# KX1_DB_EX_CONN.net
KiCad netlist of a schematic drawn in Altium Designer
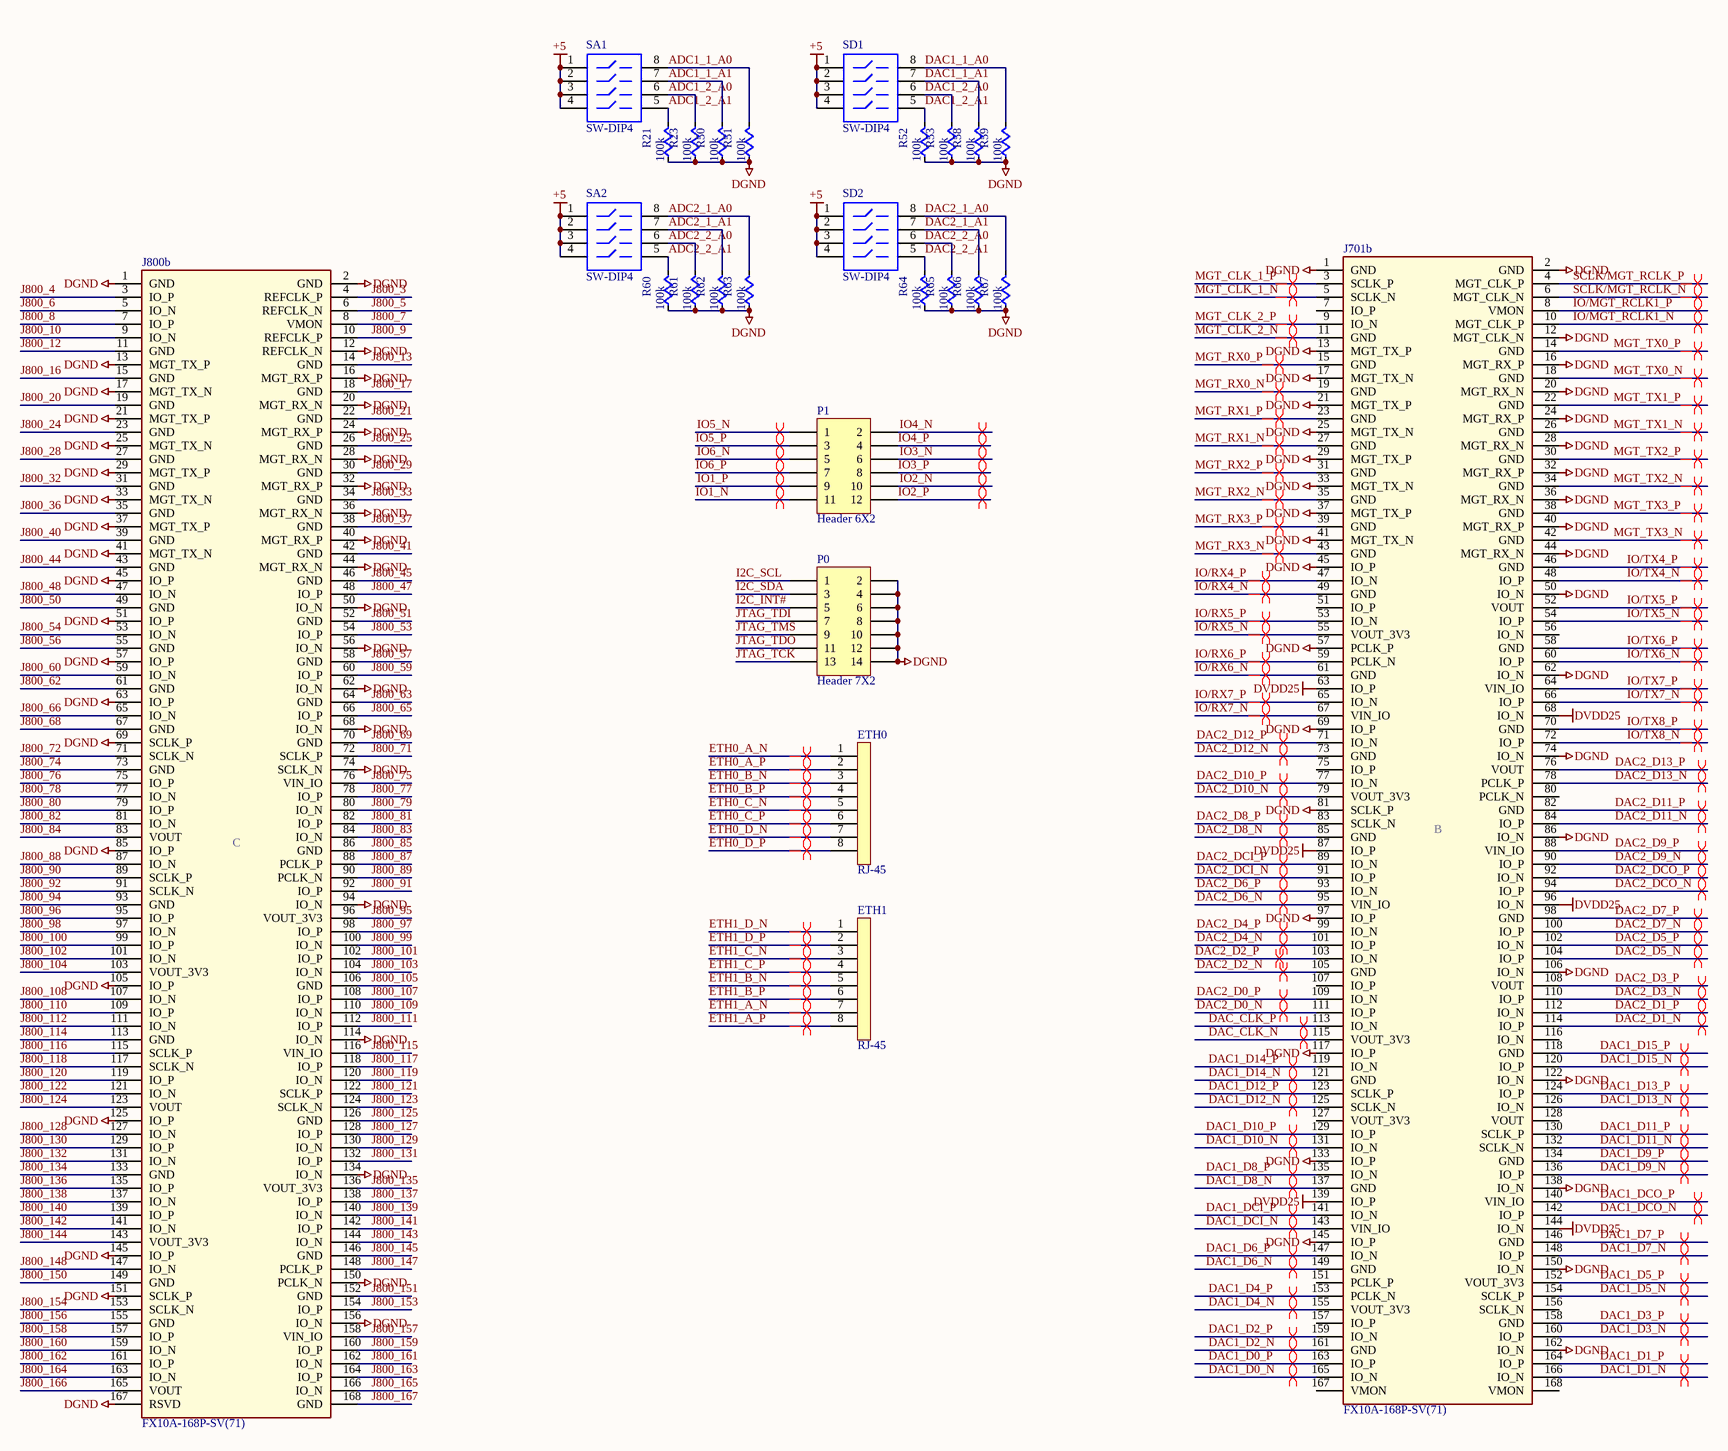
[diagram p0: KX1_DB_EX_CONN.SchDoc]

(export (version "E")
  (design (tool "Eeschema 10.0.6"))
  (components
    (comp (ref "ETH0")
      (value "RJ-45")
      (footprint "SMD_ETHERNET")
      (description "ethernet connector")
      (libsource (lib "KX1_DB") (part "SIP8"))
    )
    (comp (ref "ETH1")
      (value "RJ-45")
      (footprint "SMD_ETHERNET")
      (description "ethernet connector")
      (libsource (lib "KX1_DB") (part "SIP8"))
    )
    (comp (ref "J701b")
      (value "FX10A-168P-SV(71)")
      (footprint "Mercury_Baseboard_Connector")
      (description "Mercury Baseboard Connector")
      (fields
        (field (name "MANUFACTURER") "Hirose")
        (field (name "DISTPARTNUMBER") "FX10A-168P-SV(71)-ND")
        (field (name "CHECK SCH") "CG_2015-03-03")
      )
      (libsource (lib "Enclustra-Mars-Mercury-Altium-Library") (part "Mercury_Baseboard_Connector-B"))
    )
    (comp (ref "J800b")
      (value "FX10A-168P-SV(71)")
      (footprint "Mercury_Baseboard_Connector")
      (description "Mercury Baseboard Connector")
      (fields
        (field (name "MANUFACTURER") "Hirose")
        (field (name "DISTPARTNUMBER") "FX10A-168P-SV(71)-ND")
        (field (name "CHECK SCH") "CG_2015-03-03")
      )
      (libsource (lib "Enclustra-Mars-Mercury-Altium-Library") (part "Mercury_Baseboard_Connector-C"))
    )
    (comp (ref "P0")
      (value "Header 7X2")
      (footprint "HDR2X7")
      (description "Header, 7-Pin, Dual row")
      (fields (field (name "PUBLISHER") "Altium Limited"))
      (libsource (lib "Miscellaneous Connectors") (part "Header 7X2"))
    )
    (comp (ref "P1")
      (value "Header 6X2")
      (footprint "HDR2X6")
      (description "Header, 6-Pin, Dual row")
      (fields (field (name "PUBLISHER") "Altium Limited"))
      (libsource (lib "Miscellaneous Connectors") (part "Header 6X2"))
    )
    (comp (ref "R21")
      (value "100k")
      (footprint "0603w")
      (description "resistor")
      (fields
        (field (name "MANUFACTURER") "Yageo")
        (field (name "MANUFACTURER PART NUMBER") "RC0603FR-0776K8L")
      )
      (libsource (lib "KX1_DB") (part "RES_SM"))
    )
    (comp (ref "R23")
      (value "100k")
      (footprint "0603w")
      (description "resistor")
      (fields
        (field (name "MANUFACTURER") "Yageo")
        (field (name "MANUFACTURER PART NUMBER") "RC0603FR-0776K8L")
      )
      (libsource (lib "KX1_DB") (part "RES_SM"))
    )
    (comp (ref "R50")
      (value "100k")
      (footprint "0603w")
      (description "resistor")
      (fields
        (field (name "MANUFACTURER") "Yageo")
        (field (name "MANUFACTURER PART NUMBER") "RC0603FR-0776K8L")
      )
      (libsource (lib "KX1_DB") (part "RES_SM"))
    )
    (comp (ref "R51")
      (value "100k")
      (footprint "0603w")
      (description "resistor")
      (fields
        (field (name "MANUFACTURER") "Yageo")
        (field (name "MANUFACTURER PART NUMBER") "RC0603FR-0776K8L")
      )
      (libsource (lib "KX1_DB") (part "RES_SM"))
    )
    (comp (ref "R52")
      (value "100k")
      (footprint "0603w")
      (description "resistor")
      (fields
        (field (name "MANUFACTURER") "Yageo")
        (field (name "MANUFACTURER PART NUMBER") "RC0603FR-0776K8L")
      )
      (libsource (lib "KX1_DB") (part "RES_SM"))
    )
    (comp (ref "R53")
      (value "100k")
      (footprint "0603w")
      (description "resistor")
      (fields
        (field (name "MANUFACTURER") "Yageo")
        (field (name "MANUFACTURER PART NUMBER") "RC0603FR-0776K8L")
      )
      (libsource (lib "KX1_DB") (part "RES_SM"))
    )
    (comp (ref "R58")
      (value "100k")
      (footprint "0603w")
      (description "resistor")
      (fields
        (field (name "MANUFACTURER") "Yageo")
        (field (name "MANUFACTURER PART NUMBER") "RC0603FR-0776K8L")
      )
      (libsource (lib "KX1_DB") (part "RES_SM"))
    )
    (comp (ref "R59")
      (value "100k")
      (footprint "0603w")
      (description "resistor")
      (fields
        (field (name "MANUFACTURER") "Yageo")
        (field (name "MANUFACTURER PART NUMBER") "RC0603FR-0776K8L")
      )
      (libsource (lib "KX1_DB") (part "RES_SM"))
    )
    (comp (ref "R60")
      (value "100k")
      (footprint "0603w")
      (description "resistor")
      (fields
        (field (name "MANUFACTURER") "Yageo")
        (field (name "MANUFACTURER PART NUMBER") "RC0603FR-0776K8L")
      )
      (libsource (lib "KX1_DB") (part "RES_SM"))
    )
    (comp (ref "R61")
      (value "100k")
      (footprint "0603w")
      (description "resistor")
      (fields
        (field (name "MANUFACTURER") "Yageo")
        (field (name "MANUFACTURER PART NUMBER") "RC0603FR-0776K8L")
      )
      (libsource (lib "KX1_DB") (part "RES_SM"))
    )
    (comp (ref "R62")
      (value "100k")
      (footprint "0603w")
      (description "resistor")
      (fields
        (field (name "MANUFACTURER") "Yageo")
        (field (name "MANUFACTURER PART NUMBER") "RC0603FR-0776K8L")
      )
      (libsource (lib "KX1_DB") (part "RES_SM"))
    )
    (comp (ref "R63")
      (value "100k")
      (footprint "0603w")
      (description "resistor")
      (fields
        (field (name "MANUFACTURER") "Yageo")
        (field (name "MANUFACTURER PART NUMBER") "RC0603FR-0776K8L")
      )
      (libsource (lib "KX1_DB") (part "RES_SM"))
    )
    (comp (ref "R64")
      (value "100k")
      (footprint "0603w")
      (description "resistor")
      (fields
        (field (name "MANUFACTURER") "Yageo")
        (field (name "MANUFACTURER PART NUMBER") "RC0603FR-0776K8L")
      )
      (libsource (lib "KX1_DB") (part "RES_SM"))
    )
    (comp (ref "R65")
      (value "100k")
      (footprint "0603w")
      (description "resistor")
      (fields
        (field (name "MANUFACTURER") "Yageo")
        (field (name "MANUFACTURER PART NUMBER") "RC0603FR-0776K8L")
      )
      (libsource (lib "KX1_DB") (part "RES_SM"))
    )
    (comp (ref "R66")
      (value "100k")
      (footprint "0603w")
      (description "resistor")
      (fields
        (field (name "MANUFACTURER") "Yageo")
        (field (name "MANUFACTURER PART NUMBER") "RC0603FR-0776K8L")
      )
      (libsource (lib "KX1_DB") (part "RES_SM"))
    )
    (comp (ref "R67")
      (value "100k")
      (footprint "0603w")
      (description "resistor")
      (fields
        (field (name "MANUFACTURER") "Yageo")
        (field (name "MANUFACTURER PART NUMBER") "RC0603FR-0776K8L")
      )
      (libsource (lib "KX1_DB") (part "RES_SM"))
    )
    (comp (ref "SA1")
      (value "SW-DIP4")
      (footprint "DIP-8")
      (description "DIP Switch")
      (fields (field (name "PUBLISHER") "Altium Limited"))
      (libsource (lib "Miscellaneous Devices") (part "SW-DIP4"))
    )
    (comp (ref "SA2")
      (value "SW-DIP4")
      (footprint "DIP-8")
      (description "DIP Switch")
      (fields (field (name "PUBLISHER") "Altium Limited"))
      (libsource (lib "Miscellaneous Devices") (part "SW-DIP4"))
    )
    (comp (ref "SD1")
      (value "SW-DIP4")
      (footprint "DIP-8")
      (description "DIP Switch")
      (fields (field (name "PUBLISHER") "Altium Limited"))
      (libsource (lib "Miscellaneous Devices") (part "SW-DIP4"))
    )
    (comp (ref "SD2")
      (value "SW-DIP4")
      (footprint "DIP-8")
      (description "DIP Switch")
      (fields (field (name "PUBLISHER") "Altium Limited"))
      (libsource (lib "Miscellaneous Devices") (part "SW-DIP4"))
    )
  )
  (nets
    (net (code "1") (name "+5") (class "Default")
      (node (ref "SA1") (pin "1") (pinfunction "1_1") (pintype "passive"))
      (node (ref "SA1") (pin "2") (pinfunction "2_2") (pintype "passive"))
      (node (ref "SA1") (pin "3") (pinfunction "3_3") (pintype "passive"))
      (node (ref "SA1") (pin "4") (pinfunction "4_4") (pintype "passive"))
      (node (ref "SA2") (pin "1") (pinfunction "1_1") (pintype "passive"))
      (node (ref "SA2") (pin "2") (pinfunction "2_2") (pintype "passive"))
      (node (ref "SA2") (pin "3") (pinfunction "3_3") (pintype "passive"))
      (node (ref "SA2") (pin "4") (pinfunction "4_4") (pintype "passive"))
      (node (ref "SD1") (pin "1") (pinfunction "1_1") (pintype "passive"))
      (node (ref "SD1") (pin "2") (pinfunction "2_2") (pintype "passive"))
      (node (ref "SD1") (pin "3") (pinfunction "3_3") (pintype "passive"))
      (node (ref "SD1") (pin "4") (pinfunction "4_4") (pintype "passive"))
      (node (ref "SD2") (pin "1") (pinfunction "1_1") (pintype "passive"))
      (node (ref "SD2") (pin "2") (pinfunction "2_2") (pintype "passive"))
      (node (ref "SD2") (pin "3") (pinfunction "3_3") (pintype "passive"))
      (node (ref "SD2") (pin "4") (pinfunction "4_4") (pintype "passive"))
    )
    (net (code "2") (name "/ADC1_1_A0") (class "Default")
      (node (ref "R51") (pin "2") (pintype "passive"))
      (node (ref "SA1") (pin "8") (pinfunction "8_8") (pintype "passive"))
    )
    (net (code "3") (name "/ADC1_1_A1") (class "Default")
      (node (ref "R50") (pin "2") (pintype "passive"))
      (node (ref "SA1") (pin "7") (pinfunction "7_7") (pintype "passive"))
    )
    (net (code "4") (name "/ADC1_2_A0") (class "Default")
      (node (ref "R23") (pin "2") (pintype "passive"))
      (node (ref "SA1") (pin "6") (pinfunction "6_6") (pintype "passive"))
    )
    (net (code "5") (name "/ADC1_2_A1") (class "Default")
      (node (ref "R21") (pin "2") (pintype "passive"))
      (node (ref "SA1") (pin "5") (pinfunction "5_5") (pintype "passive"))
    )
    (net (code "6") (name "/ADC2_1_A0") (class "Default")
      (node (ref "R63") (pin "2") (pintype "passive"))
      (node (ref "SA2") (pin "8") (pinfunction "8_8") (pintype "passive"))
    )
    (net (code "7") (name "/ADC2_1_A1") (class "Default")
      (node (ref "R62") (pin "2") (pintype "passive"))
      (node (ref "SA2") (pin "7") (pinfunction "7_7") (pintype "passive"))
    )
    (net (code "8") (name "/ADC2_2_A0") (class "Default")
      (node (ref "R61") (pin "2") (pintype "passive"))
      (node (ref "SA2") (pin "6") (pinfunction "6_6") (pintype "passive"))
    )
    (net (code "9") (name "/ADC2_2_A1") (class "Default")
      (node (ref "R60") (pin "2") (pintype "passive"))
      (node (ref "SA2") (pin "5") (pinfunction "5_5") (pintype "passive"))
    )
    (net (code "10") (name "/DAC1_1_A0") (class "Default")
      (node (ref "R59") (pin "2") (pintype "passive"))
      (node (ref "SD1") (pin "8") (pinfunction "8_8") (pintype "passive"))
    )
    (net (code "11") (name "/DAC1_1_A1") (class "Default")
      (node (ref "R58") (pin "2") (pintype "passive"))
      (node (ref "SD1") (pin "7") (pinfunction "7_7") (pintype "passive"))
    )
    (net (code "12") (name "/DAC1_2_A0") (class "Default")
      (node (ref "R53") (pin "2") (pintype "passive"))
      (node (ref "SD1") (pin "6") (pinfunction "6_6") (pintype "passive"))
    )
    (net (code "13") (name "/DAC1_2_A1") (class "Default")
      (node (ref "R52") (pin "2") (pintype "passive"))
      (node (ref "SD1") (pin "5") (pinfunction "5_5") (pintype "passive"))
    )
    (net (code "14") (name "/DAC1_D0_N") (class "Default")
      (node (ref "J701b") (pin "165") (pinfunction "IO_N_165") (pintype "passive"))
    )
    (net (code "15") (name "/DAC1_D0_P") (class "Default")
      (node (ref "J701b") (pin "163") (pinfunction "IO_P_163") (pintype "passive"))
    )
    (net (code "16") (name "/DAC1_D1_N") (class "Default")
      (node (ref "J701b") (pin "166") (pinfunction "IO_N_166") (pintype "passive"))
    )
    (net (code "17") (name "/DAC1_D1_P") (class "Default")
      (node (ref "J701b") (pin "164") (pinfunction "IO_P_164") (pintype "passive"))
    )
    (net (code "18") (name "/DAC1_D2_N") (class "Default")
      (node (ref "J701b") (pin "161") (pinfunction "GND_161") (pintype "passive"))
    )
    (net (code "19") (name "/DAC1_D2_P") (class "Default")
      (node (ref "J701b") (pin "159") (pinfunction "IO_N_159") (pintype "passive"))
    )
    (net (code "20") (name "/DAC1_D3_N") (class "Default")
      (node (ref "J701b") (pin "160") (pinfunction "IO_P_160") (pintype "passive"))
    )
    (net (code "21") (name "/DAC1_D3_P") (class "Default")
      (node (ref "J701b") (pin "158") (pinfunction "GND_158") (pintype "passive"))
    )
    (net (code "22") (name "/DAC1_D4_N") (class "Default")
      (node (ref "J701b") (pin "155") (pinfunction "VOUT_3V3_155") (pintype "passive"))
    )
    (net (code "23") (name "/DAC1_D4_P") (class "Default")
      (node (ref "J701b") (pin "153") (pinfunction "PCLK_N_153") (pintype "passive"))
    )
    (net (code "24") (name "/DAC1_D5_N") (class "Default")
      (node (ref "J701b") (pin "154") (pinfunction "SCLK_P_154") (pintype "passive"))
    )
    (net (code "25") (name "/DAC1_D5_P") (class "Default")
      (node (ref "J701b") (pin "152") (pinfunction "VOUT_3V3_152") (pintype "passive"))
    )
    (net (code "26") (name "/DAC1_D6_N") (class "Default")
      (node (ref "J701b") (pin "149") (pinfunction "GND_149") (pintype "passive"))
    )
    (net (code "27") (name "/DAC1_D6_P") (class "Default")
      (node (ref "J701b") (pin "147") (pinfunction "IO_N_147") (pintype "passive"))
    )
    (net (code "28") (name "/DAC1_D7_N") (class "Default")
      (node (ref "J701b") (pin "148") (pinfunction "IO_P_148") (pintype "passive"))
    )
    (net (code "29") (name "/DAC1_D7_P") (class "Default")
      (node (ref "J701b") (pin "146") (pinfunction "GND_146") (pintype "passive"))
    )
    (net (code "30") (name "/DAC1_D8_N") (class "Default")
      (node (ref "J701b") (pin "137") (pinfunction "GND_137") (pintype "passive"))
    )
    (net (code "31") (name "/DAC1_D8_P") (class "Default")
      (node (ref "J701b") (pin "135") (pinfunction "IO_N_135") (pintype "passive"))
    )
    (net (code "32") (name "/DAC1_D9_N") (class "Default")
      (node (ref "J701b") (pin "136") (pinfunction "IO_P_136") (pintype "passive"))
    )
    (net (code "33") (name "/DAC1_D9_P") (class "Default")
      (node (ref "J701b") (pin "134") (pinfunction "GND_134") (pintype "passive"))
    )
    (net (code "34") (name "/DAC1_D10_N") (class "Default")
      (node (ref "J701b") (pin "131") (pinfunction "IO_N_131") (pintype "passive"))
    )
    (net (code "35") (name "/DAC1_D10_P") (class "Default")
      (node (ref "J701b") (pin "129") (pinfunction "IO_P_129") (pintype "passive"))
    )
    (net (code "36") (name "/DAC1_D11_N") (class "Default")
      (node (ref "J701b") (pin "132") (pinfunction "SCLK_N_132") (pintype "passive"))
    )
    (net (code "37") (name "/DAC1_D11_P") (class "Default")
      (node (ref "J701b") (pin "130") (pinfunction "SCLK_P_130") (pintype "passive"))
    )
    (net (code "38") (name "/DAC1_D12_N") (class "Default")
      (node (ref "J701b") (pin "125") (pinfunction "SCLK_N_125") (pintype "passive"))
    )
    (net (code "39") (name "/DAC1_D12_P") (class "Default")
      (node (ref "J701b") (pin "123") (pinfunction "SCLK_P_123") (pintype "passive"))
    )
    (net (code "40") (name "/DAC1_D13_N") (class "Default")
      (node (ref "J701b") (pin "126") (pinfunction "IO_N_126") (pintype "passive"))
    )
    (net (code "41") (name "/DAC1_D13_P") (class "Default")
      (node (ref "J701b") (pin "124") (pinfunction "IO_P_124") (pintype "passive"))
    )
    (net (code "42") (name "/DAC1_D14_N") (class "Default")
      (node (ref "J701b") (pin "121") (pinfunction "GND_121") (pintype "passive"))
    )
    (net (code "43") (name "/DAC1_D14_P") (class "Default")
      (node (ref "J701b") (pin "119") (pinfunction "IO_N_119") (pintype "passive"))
    )
    (net (code "44") (name "/DAC1_D15_N") (class "Default")
      (node (ref "J701b") (pin "120") (pinfunction "IO_P_120") (pintype "passive"))
    )
    (net (code "45") (name "/DAC1_D15_P") (class "Default")
      (node (ref "J701b") (pin "118") (pinfunction "GND_118") (pintype "passive"))
    )
    (net (code "46") (name "/DAC1_DCI_N") (class "Default")
      (node (ref "J701b") (pin "143") (pinfunction "VIN_IO_143") (pintype "passive"))
    )
    (net (code "47") (name "/DAC1_DCI_P") (class "Default")
      (node (ref "J701b") (pin "141") (pinfunction "IO_N_141") (pintype "passive"))
    )
    (net (code "48") (name "/DAC1_DCO_N") (class "Default")
      (node (ref "J701b") (pin "142") (pinfunction "IO_P_142") (pintype "passive"))
    )
    (net (code "49") (name "/DAC1_DCO_P") (class "Default")
      (node (ref "J701b") (pin "140") (pinfunction "VIN_IO_140") (pintype "passive"))
    )
    (net (code "50") (name "/DAC2_1_A0") (class "Default")
      (node (ref "R67") (pin "2") (pintype "passive"))
      (node (ref "SD2") (pin "8") (pinfunction "8_8") (pintype "passive"))
    )
    (net (code "51") (name "/DAC2_1_A1") (class "Default")
      (node (ref "R66") (pin "2") (pintype "passive"))
      (node (ref "SD2") (pin "7") (pinfunction "7_7") (pintype "passive"))
    )
    (net (code "52") (name "/DAC2_2_A0") (class "Default")
      (node (ref "R65") (pin "2") (pintype "passive"))
      (node (ref "SD2") (pin "6") (pinfunction "6_6") (pintype "passive"))
    )
    (net (code "53") (name "/DAC2_2_A1") (class "Default")
      (node (ref "R64") (pin "2") (pintype "passive"))
      (node (ref "SD2") (pin "5") (pinfunction "5_5") (pintype "passive"))
    )
    (net (code "54") (name "/DAC2_D0_N") (class "Default")
      (node (ref "J701b") (pin "111") (pinfunction "IO_P_111") (pintype "passive"))
    )
    (net (code "55") (name "/DAC2_D0_P") (class "Default")
      (node (ref "J701b") (pin "109") (pinfunction "IO_N_109") (pintype "passive"))
    )
    (net (code "56") (name "/DAC2_D1_N") (class "Default")
      (node (ref "J701b") (pin "114") (pinfunction "IO_P_114") (pintype "passive"))
    )
    (net (code "57") (name "/DAC2_D1_P") (class "Default")
      (node (ref "J701b") (pin "112") (pinfunction "IO_N_112") (pintype "passive"))
    )
    (net (code "58") (name "/DAC2_D2_N") (class "Default")
      (node (ref "J701b") (pin "105") (pinfunction "GND_105") (pintype "passive"))
    )
    (net (code "59") (name "/DAC2_D2_P") (class "Default")
      (node (ref "J701b") (pin "103") (pinfunction "IO_N_103") (pintype "passive"))
    )
    (net (code "60") (name "/DAC2_D3_N") (class "Default")
      (node (ref "J701b") (pin "110") (pinfunction "IO_P_110") (pintype "passive"))
    )
    (net (code "61") (name "/DAC2_D3_P") (class "Default")
      (node (ref "J701b") (pin "108") (pinfunction "VOUT_108") (pintype "passive"))
    )
    (net (code "62") (name "/DAC2_D4_N") (class "Default")
      (node (ref "J701b") (pin "101") (pinfunction "IO_P_101") (pintype "passive"))
    )
    (net (code "63") (name "/DAC2_D4_P") (class "Default")
      (node (ref "J701b") (pin "99") (pinfunction "IO_N_99") (pintype "passive"))
    )
    (net (code "64") (name "/DAC2_D5_N") (class "Default")
      (node (ref "J701b") (pin "104") (pinfunction "IO_P_104") (pintype "passive"))
    )
    (net (code "65") (name "/DAC2_D5_P") (class "Default")
      (node (ref "J701b") (pin "102") (pinfunction "IO_N_102") (pintype "passive"))
    )
    (net (code "66") (name "/DAC2_D6_N") (class "Default")
      (node (ref "J701b") (pin "95") (pinfunction "VIN_IO_95") (pintype "passive"))
    )
    (net (code "67") (name "/DAC2_D6_P") (class "Default")
      (node (ref "J701b") (pin "93") (pinfunction "IO_N_93") (pintype "passive"))
    )
    (net (code "68") (name "/DAC2_D7_N") (class "Default")
      (node (ref "J701b") (pin "100") (pinfunction "IO_P_100") (pintype "passive"))
    )
    (net (code "69") (name "/DAC2_D7_P") (class "Default")
      (node (ref "J701b") (pin "98") (pinfunction "GND_98") (pintype "passive"))
    )
    (net (code "70") (name "/DAC2_D8_N") (class "Default")
      (node (ref "J701b") (pin "85") (pinfunction "GND_85") (pintype "passive"))
    )
    (net (code "71") (name "/DAC2_D8_P") (class "Default")
      (node (ref "J701b") (pin "83") (pinfunction "SCLK_N_83") (pintype "passive"))
    )
    (net (code "72") (name "/DAC2_D9_N") (class "Default")
      (node (ref "J701b") (pin "90") (pinfunction "IO_P_90") (pintype "passive"))
    )
    (net (code "73") (name "/DAC2_D9_P") (class "Default")
      (node (ref "J701b") (pin "88") (pinfunction "VIN_IO_88") (pintype "passive"))
    )
    (net (code "74") (name "/DAC2_D10_N") (class "Default")
      (node (ref "J701b") (pin "79") (pinfunction "VOUT_3V3_79") (pintype "passive"))
    )
    (net (code "75") (name "/DAC2_D10_P") (class "Default")
      (node (ref "J701b") (pin "77") (pinfunction "IO_N_77") (pintype "passive"))
    )
    (net (code "76") (name "/DAC2_D11_N") (class "Default")
      (node (ref "J701b") (pin "84") (pinfunction "IO_P_84") (pintype "passive"))
    )
    (net (code "77") (name "/DAC2_D11_P") (class "Default")
      (node (ref "J701b") (pin "82") (pinfunction "GND_82") (pintype "passive"))
    )
    (net (code "78") (name "/DAC2_D12_N") (class "Default")
      (node (ref "J701b") (pin "73") (pinfunction "GND_73") (pintype "passive"))
    )
    (net (code "79") (name "/DAC2_D12_P") (class "Default")
      (node (ref "J701b") (pin "71") (pinfunction "IO_N_71") (pintype "passive"))
    )
    (net (code "80") (name "/DAC2_D13_N") (class "Default")
      (node (ref "J701b") (pin "78") (pinfunction "PCLK_P_78") (pintype "passive"))
    )
    (net (code "81") (name "/DAC2_D13_P") (class "Default")
      (node (ref "J701b") (pin "76") (pinfunction "VOUT_76") (pintype "passive"))
    )
    (net (code "82") (name "/DAC2_DCI_N") (class "Default")
      (node (ref "J701b") (pin "91") (pinfunction "IO_P_91") (pintype "passive"))
    )
    (net (code "83") (name "/DAC2_DCI_P") (class "Default")
      (node (ref "J701b") (pin "89") (pinfunction "IO_N_89") (pintype "passive"))
    )
    (net (code "84") (name "/DAC2_DCO_N") (class "Default")
      (node (ref "J701b") (pin "94") (pinfunction "IO_P_94") (pintype "passive"))
    )
    (net (code "85") (name "/DAC2_DCO_P") (class "Default")
      (node (ref "J701b") (pin "92") (pinfunction "IO_N_92") (pintype "passive"))
    )
    (net (code "86") (name "/DAC_CLK_N") (class "Default")
      (node (ref "J701b") (pin "115") (pinfunction "VOUT_3V3_115") (pintype "passive"))
    )
    (net (code "87") (name "/DAC_CLK_P") (class "Default")
      (node (ref "J701b") (pin "113") (pinfunction "IO_N_113") (pintype "passive"))
    )
    (net (code "88") (name "/ETH0_A_N") (class "Default") (node (ref "ETH0") (pin "1") (pintype "passive")))
    (net (code "89") (name "/ETH0_A_P") (class "Default") (node (ref "ETH0") (pin "2") (pintype "passive")))
    (net (code "90") (name "/ETH0_B_N") (class "Default") (node (ref "ETH0") (pin "3") (pintype "passive")))
    (net (code "91") (name "/ETH0_B_P") (class "Default") (node (ref "ETH0") (pin "4") (pintype "passive")))
    (net (code "92") (name "/ETH0_C_N") (class "Default") (node (ref "ETH0") (pin "5") (pintype "passive")))
    (net (code "93") (name "/ETH0_C_P") (class "Default") (node (ref "ETH0") (pin "6") (pintype "passive")))
    (net (code "94") (name "/ETH0_D_N") (class "Default") (node (ref "ETH0") (pin "7") (pintype "passive")))
    (net (code "95") (name "/ETH0_D_P") (class "Default") (node (ref "ETH0") (pin "8") (pintype "passive")))
    (net (code "96") (name "/ETH1_A_N") (class "Default") (node (ref "ETH1") (pin "7") (pintype "passive")))
    (net (code "97") (name "/ETH1_A_P") (class "Default") (node (ref "ETH1") (pin "8") (pintype "passive")))
    (net (code "98") (name "/ETH1_B_N") (class "Default") (node (ref "ETH1") (pin "5") (pintype "passive")))
    (net (code "99") (name "/ETH1_B_P") (class "Default") (node (ref "ETH1") (pin "6") (pintype "passive")))
    (net (code "100") (name "/ETH1_C_N") (class "Default") (node (ref "ETH1") (pin "3") (pintype "passive")))
    (net (code "101") (name "/ETH1_C_P") (class "Default") (node (ref "ETH1") (pin "4") (pintype "passive")))
    (net (code "102") (name "/ETH1_D_N") (class "Default") (node (ref "ETH1") (pin "1") (pintype "passive")))
    (net (code "103") (name "/ETH1_D_P") (class "Default") (node (ref "ETH1") (pin "2") (pintype "passive")))
    (net (code "104") (name "/I2C_INT#") (class "Default")
      (node (ref "P0") (pin "5") (pinfunction "5_5") (pintype "passive"))
    )
    (net (code "105") (name "/I2C_SCL") (class "Default")
      (node (ref "P0") (pin "1") (pinfunction "1_1") (pintype "passive"))
    )
    (net (code "106") (name "/I2C_SDA") (class "Default")
      (node (ref "P0") (pin "3") (pinfunction "3_3") (pintype "passive"))
    )
    (net (code "107") (name "/IO1_N") (class "Default")
      (node (ref "P1") (pin "11") (pinfunction "11_11") (pintype "passive"))
    )
    (net (code "108") (name "/IO1_P") (class "Default")
      (node (ref "P1") (pin "9") (pinfunction "9_9") (pintype "passive"))
    )
    (net (code "109") (name "/IO2_N") (class "Default")
      (node (ref "P1") (pin "10") (pinfunction "10_10") (pintype "passive"))
    )
    (net (code "110") (name "/IO2_P") (class "Default")
      (node (ref "P1") (pin "12") (pinfunction "12_12") (pintype "passive"))
    )
    (net (code "111") (name "/IO3_N") (class "Default")
      (node (ref "P1") (pin "6") (pinfunction "6_6") (pintype "passive"))
    )
    (net (code "112") (name "/IO3_P") (class "Default")
      (node (ref "P1") (pin "8") (pinfunction "8_8") (pintype "passive"))
    )
    (net (code "113") (name "/IO4_N") (class "Default")
      (node (ref "P1") (pin "2") (pinfunction "2_2") (pintype "passive"))
    )
    (net (code "114") (name "/IO4_P") (class "Default")
      (node (ref "P1") (pin "4") (pinfunction "4_4") (pintype "passive"))
    )
    (net (code "115") (name "/IO5_N") (class "Default")
      (node (ref "P1") (pin "1") (pinfunction "1_1") (pintype "passive"))
    )
    (net (code "116") (name "/IO5_P") (class "Default")
      (node (ref "P1") (pin "3") (pinfunction "3_3") (pintype "passive"))
    )
    (net (code "117") (name "/IO6_N") (class "Default")
      (node (ref "P1") (pin "5") (pinfunction "5_5") (pintype "passive"))
    )
    (net (code "118") (name "/IO6_P") (class "Default")
      (node (ref "P1") (pin "7") (pinfunction "7_7") (pintype "passive"))
    )
    (net (code "119") (name "/IO{slash}MGT_RCLK1_N") (class "Default")
      (node (ref "J701b") (pin "10") (pinfunction "MGT_CLK_P_10") (pintype "passive"))
    )
    (net (code "120") (name "/IO{slash}MGT_RCLK1_P") (class "Default")
      (node (ref "J701b") (pin "8") (pinfunction "VMON_8") (pintype "passive"))
    )
    (net (code "121") (name "/IO{slash}RX4_N") (class "Default")
      (node (ref "J701b") (pin "49") (pinfunction "GND_49") (pintype "passive"))
    )
    (net (code "122") (name "/IO{slash}RX4_P") (class "Default")
      (node (ref "J701b") (pin "47") (pinfunction "IO_N_47") (pintype "passive"))
    )
    (net (code "123") (name "/IO{slash}RX5_N") (class "Default")
      (node (ref "J701b") (pin "55") (pinfunction "VOUT_3V3_55") (pintype "passive"))
    )
    (net (code "124") (name "/IO{slash}RX5_P") (class "Default")
      (node (ref "J701b") (pin "53") (pinfunction "IO_N_53") (pintype "passive"))
    )
    (net (code "125") (name "/IO{slash}RX6_N") (class "Default")
      (node (ref "J701b") (pin "61") (pinfunction "GND_61") (pintype "passive"))
    )
    (net (code "126") (name "/IO{slash}RX6_P") (class "Default")
      (node (ref "J701b") (pin "59") (pinfunction "PCLK_N_59") (pintype "passive"))
    )
    (net (code "127") (name "/IO{slash}RX7_N") (class "Default")
      (node (ref "J701b") (pin "67") (pinfunction "VIN_IO_67") (pintype "passive"))
    )
    (net (code "128") (name "/IO{slash}RX7_P") (class "Default")
      (node (ref "J701b") (pin "65") (pinfunction "IO_N_65") (pintype "passive"))
    )
    (net (code "129") (name "/IO{slash}TX4_N") (class "Default")
      (node (ref "J701b") (pin "48") (pinfunction "IO_P_48") (pintype "passive"))
    )
    (net (code "130") (name "/IO{slash}TX4_P") (class "Default")
      (node (ref "J701b") (pin "46") (pinfunction "GND_46") (pintype "passive"))
    )
    (net (code "131") (name "/IO{slash}TX5_N") (class "Default")
      (node (ref "J701b") (pin "54") (pinfunction "IO_P_54") (pintype "passive"))
    )
    (net (code "132") (name "/IO{slash}TX5_P") (class "Default")
      (node (ref "J701b") (pin "52") (pinfunction "VOUT_52") (pintype "passive"))
    )
    (net (code "133") (name "/IO{slash}TX6_N") (class "Default")
      (node (ref "J701b") (pin "60") (pinfunction "IO_P_60") (pintype "passive"))
    )
    (net (code "134") (name "/IO{slash}TX6_P") (class "Default")
      (node (ref "J701b") (pin "58") (pinfunction "GND_58") (pintype "passive"))
    )
    (net (code "135") (name "/IO{slash}TX7_N") (class "Default")
      (node (ref "J701b") (pin "66") (pinfunction "IO_P_66") (pintype "passive"))
    )
    (net (code "136") (name "/IO{slash}TX7_P") (class "Default")
      (node (ref "J701b") (pin "64") (pinfunction "VIN_IO_64") (pintype "passive"))
    )
    (net (code "137") (name "/IO{slash}TX8_N") (class "Default")
      (node (ref "J701b") (pin "72") (pinfunction "IO_P_72") (pintype "passive"))
    )
    (net (code "138") (name "/IO{slash}TX8_P") (class "Default")
      (node (ref "J701b") (pin "70") (pinfunction "GND_70") (pintype "passive"))
    )
    (net (code "139") (name "/J800_3") (class "Default")
      (node (ref "J800b") (pin "4") (pinfunction "REFCLK_P_4") (pintype "passive"))
    )
    (net (code "140") (name "/J800_4") (class "Default")
      (node (ref "J800b") (pin "3") (pinfunction "IO_P_3") (pintype "passive"))
    )
    (net (code "141") (name "/J800_5") (class "Default")
      (node (ref "J800b") (pin "6") (pinfunction "REFCLK_N_6") (pintype "passive"))
    )
    (net (code "142") (name "/J800_6") (class "Default")
      (node (ref "J800b") (pin "5") (pinfunction "IO_N_5") (pintype "passive"))
    )
    (net (code "143") (name "/J800_7") (class "Default")
      (node (ref "J800b") (pin "8") (pinfunction "VMON_8") (pintype "passive"))
    )
    (net (code "144") (name "/J800_8") (class "Default")
      (node (ref "J800b") (pin "7") (pinfunction "IO_P_7") (pintype "passive"))
    )
    (net (code "145") (name "/J800_9") (class "Default")
      (node (ref "J800b") (pin "10") (pinfunction "REFCLK_P_10") (pintype "passive"))
    )
    (net (code "146") (name "/J800_10") (class "Default")
      (node (ref "J800b") (pin "9") (pinfunction "IO_N_9") (pintype "passive"))
    )
    (net (code "147") (name "/J800_12") (class "Default")
      (node (ref "J800b") (pin "11") (pinfunction "GND_11") (pintype "passive"))
    )
    (net (code "148") (name "/J800_13") (class "Default")
      (node (ref "J800b") (pin "14") (pinfunction "GND_14") (pintype "passive"))
    )
    (net (code "149") (name "/J800_16") (class "Default")
      (node (ref "J800b") (pin "15") (pinfunction "GND_15") (pintype "passive"))
    )
    (net (code "150") (name "/J800_17") (class "Default")
      (node (ref "J800b") (pin "18") (pinfunction "GND_18") (pintype "passive"))
    )
    (net (code "151") (name "/J800_20") (class "Default")
      (node (ref "J800b") (pin "19") (pinfunction "GND_19") (pintype "passive"))
    )
    (net (code "152") (name "/J800_21") (class "Default")
      (node (ref "J800b") (pin "22") (pinfunction "GND_22") (pintype "passive"))
    )
    (net (code "153") (name "/J800_24") (class "Default")
      (node (ref "J800b") (pin "23") (pinfunction "GND_23") (pintype "passive"))
    )
    (net (code "154") (name "/J800_25") (class "Default")
      (node (ref "J800b") (pin "26") (pinfunction "GND_26") (pintype "passive"))
    )
    (net (code "155") (name "/J800_28") (class "Default")
      (node (ref "J800b") (pin "27") (pinfunction "GND_27") (pintype "passive"))
    )
    (net (code "156") (name "/J800_29") (class "Default")
      (node (ref "J800b") (pin "30") (pinfunction "GND_30") (pintype "passive"))
    )
    (net (code "157") (name "/J800_32") (class "Default")
      (node (ref "J800b") (pin "31") (pinfunction "GND_31") (pintype "passive"))
    )
    (net (code "158") (name "/J800_33") (class "Default")
      (node (ref "J800b") (pin "34") (pinfunction "GND_34") (pintype "passive"))
    )
    (net (code "159") (name "/J800_36") (class "Default")
      (node (ref "J800b") (pin "35") (pinfunction "GND_35") (pintype "passive"))
    )
    (net (code "160") (name "/J800_37") (class "Default")
      (node (ref "J800b") (pin "38") (pinfunction "GND_38") (pintype "passive"))
    )
    (net (code "161") (name "/J800_40") (class "Default")
      (node (ref "J800b") (pin "39") (pinfunction "GND_39") (pintype "passive"))
    )
    (net (code "162") (name "/J800_41") (class "Default")
      (node (ref "J800b") (pin "42") (pinfunction "GND_42") (pintype "passive"))
    )
    (net (code "163") (name "/J800_44") (class "Default")
      (node (ref "J800b") (pin "43") (pinfunction "GND_43") (pintype "passive"))
    )
    (net (code "164") (name "/J800_45") (class "Default")
      (node (ref "J800b") (pin "46") (pinfunction "GND_46") (pintype "passive"))
    )
    (net (code "165") (name "/J800_47") (class "Default")
      (node (ref "J800b") (pin "48") (pinfunction "IO_P_48") (pintype "passive"))
    )
    (net (code "166") (name "/J800_48") (class "Default")
      (node (ref "J800b") (pin "47") (pinfunction "IO_N_47") (pintype "passive"))
    )
    (net (code "167") (name "/J800_50") (class "Default")
      (node (ref "J800b") (pin "49") (pinfunction "GND_49") (pintype "passive"))
    )
    (net (code "168") (name "/J800_51") (class "Default")
      (node (ref "J800b") (pin "52") (pinfunction "GND_52") (pintype "passive"))
    )
    (net (code "169") (name "/J800_53") (class "Default")
      (node (ref "J800b") (pin "54") (pinfunction "IO_P_54") (pintype "passive"))
    )
    (net (code "170") (name "/J800_54") (class "Default")
      (node (ref "J800b") (pin "53") (pinfunction "IO_N_53") (pintype "passive"))
    )
    (net (code "171") (name "/J800_56") (class "Default")
      (node (ref "J800b") (pin "55") (pinfunction "GND_55") (pintype "passive"))
    )
    (net (code "172") (name "/J800_57") (class "Default")
      (node (ref "J800b") (pin "58") (pinfunction "GND_58") (pintype "passive"))
    )
    (net (code "173") (name "/J800_59") (class "Default")
      (node (ref "J800b") (pin "60") (pinfunction "IO_P_60") (pintype "passive"))
    )
    (net (code "174") (name "/J800_60") (class "Default")
      (node (ref "J800b") (pin "59") (pinfunction "IO_N_59") (pintype "passive"))
    )
    (net (code "175") (name "/J800_62") (class "Default")
      (node (ref "J800b") (pin "61") (pinfunction "GND_61") (pintype "passive"))
    )
    (net (code "176") (name "/J800_63") (class "Default")
      (node (ref "J800b") (pin "64") (pinfunction "GND_64") (pintype "passive"))
    )
    (net (code "177") (name "/J800_65") (class "Default")
      (node (ref "J800b") (pin "66") (pinfunction "IO_P_66") (pintype "passive"))
    )
    (net (code "178") (name "/J800_66") (class "Default")
      (node (ref "J800b") (pin "65") (pinfunction "IO_N_65") (pintype "passive"))
    )
    (net (code "179") (name "/J800_68") (class "Default")
      (node (ref "J800b") (pin "67") (pinfunction "GND_67") (pintype "passive"))
    )
    (net (code "180") (name "/J800_69") (class "Default")
      (node (ref "J800b") (pin "70") (pinfunction "GND_70") (pintype "passive"))
    )
    (net (code "181") (name "/J800_71") (class "Default")
      (node (ref "J800b") (pin "72") (pinfunction "SCLK_P_72") (pintype "passive"))
    )
    (net (code "182") (name "/J800_72") (class "Default")
      (node (ref "J800b") (pin "71") (pinfunction "SCLK_N_71") (pintype "passive"))
    )
    (net (code "183") (name "/J800_74") (class "Default")
      (node (ref "J800b") (pin "73") (pinfunction "GND_73") (pintype "passive"))
    )
    (net (code "184") (name "/J800_75") (class "Default")
      (node (ref "J800b") (pin "76") (pinfunction "VIN_IO_76") (pintype "passive"))
    )
    (net (code "185") (name "/J800_76") (class "Default")
      (node (ref "J800b") (pin "75") (pinfunction "IO_P_75") (pintype "passive"))
    )
    (net (code "186") (name "/J800_77") (class "Default")
      (node (ref "J800b") (pin "78") (pinfunction "IO_P_78") (pintype "passive"))
    )
    (net (code "187") (name "/J800_78") (class "Default")
      (node (ref "J800b") (pin "77") (pinfunction "IO_N_77") (pintype "passive"))
    )
    (net (code "188") (name "/J800_79") (class "Default")
      (node (ref "J800b") (pin "80") (pinfunction "IO_N_80") (pintype "passive"))
    )
    (net (code "189") (name "/J800_80") (class "Default")
      (node (ref "J800b") (pin "79") (pinfunction "IO_P_79") (pintype "passive"))
    )
    (net (code "190") (name "/J800_81") (class "Default")
      (node (ref "J800b") (pin "82") (pinfunction "IO_P_82") (pintype "passive"))
    )
    (net (code "191") (name "/J800_82") (class "Default")
      (node (ref "J800b") (pin "81") (pinfunction "IO_N_81") (pintype "passive"))
    )
    (net (code "192") (name "/J800_83") (class "Default")
      (node (ref "J800b") (pin "84") (pinfunction "IO_N_84") (pintype "passive"))
    )
    (net (code "193") (name "/J800_84") (class "Default")
      (node (ref "J800b") (pin "83") (pinfunction "VOUT_83") (pintype "passive"))
    )
    (net (code "194") (name "/J800_85") (class "Default")
      (node (ref "J800b") (pin "86") (pinfunction "GND_86") (pintype "passive"))
    )
    (net (code "195") (name "/J800_87") (class "Default")
      (node (ref "J800b") (pin "88") (pinfunction "PCLK_P_88") (pintype "passive"))
    )
    (net (code "196") (name "/J800_88") (class "Default")
      (node (ref "J800b") (pin "87") (pinfunction "IO_N_87") (pintype "passive"))
    )
    (net (code "197") (name "/J800_89") (class "Default")
      (node (ref "J800b") (pin "90") (pinfunction "PCLK_N_90") (pintype "passive"))
    )
    (net (code "198") (name "/J800_90") (class "Default")
      (node (ref "J800b") (pin "89") (pinfunction "SCLK_P_89") (pintype "passive"))
    )
    (net (code "199") (name "/J800_91") (class "Default")
      (node (ref "J800b") (pin "92") (pinfunction "IO_P_92") (pintype "passive"))
    )
    (net (code "200") (name "/J800_92") (class "Default")
      (node (ref "J800b") (pin "91") (pinfunction "SCLK_N_91") (pintype "passive"))
    )
    (net (code "201") (name "/J800_94") (class "Default")
      (node (ref "J800b") (pin "93") (pinfunction "GND_93") (pintype "passive"))
    )
    (net (code "202") (name "/J800_95") (class "Default")
      (node (ref "J800b") (pin "96") (pinfunction "VOUT_3V3_96") (pintype "passive"))
    )
    (net (code "203") (name "/J800_96") (class "Default")
      (node (ref "J800b") (pin "95") (pinfunction "IO_P_95") (pintype "passive"))
    )
    (net (code "204") (name "/J800_97") (class "Default")
      (node (ref "J800b") (pin "98") (pinfunction "IO_P_98") (pintype "passive"))
    )
    (net (code "205") (name "/J800_98") (class "Default")
      (node (ref "J800b") (pin "97") (pinfunction "IO_N_97") (pintype "passive"))
    )
    (net (code "206") (name "/J800_99") (class "Default")
      (node (ref "J800b") (pin "100") (pinfunction "IO_N_100") (pintype "passive"))
    )
    (net (code "207") (name "/J800_100") (class "Default")
      (node (ref "J800b") (pin "99") (pinfunction "IO_P_99") (pintype "passive"))
    )
    (net (code "208") (name "/J800_101") (class "Default")
      (node (ref "J800b") (pin "102") (pinfunction "IO_P_102") (pintype "passive"))
    )
    (net (code "209") (name "/J800_102") (class "Default")
      (node (ref "J800b") (pin "101") (pinfunction "IO_N_101") (pintype "passive"))
    )
    (net (code "210") (name "/J800_103") (class "Default")
      (node (ref "J800b") (pin "104") (pinfunction "IO_N_104") (pintype "passive"))
    )
    (net (code "211") (name "/J800_104") (class "Default")
      (node (ref "J800b") (pin "103") (pinfunction "VOUT_3V3_103") (pintype "passive"))
    )
    (net (code "212") (name "/J800_105") (class "Default")
      (node (ref "J800b") (pin "106") (pinfunction "GND_106") (pintype "passive"))
    )
    (net (code "213") (name "/J800_107") (class "Default")
      (node (ref "J800b") (pin "108") (pinfunction "IO_P_108") (pintype "passive"))
    )
    (net (code "214") (name "/J800_108") (class "Default")
      (node (ref "J800b") (pin "107") (pinfunction "IO_N_107") (pintype "passive"))
    )
    (net (code "215") (name "/J800_109") (class "Default")
      (node (ref "J800b") (pin "110") (pinfunction "IO_N_110") (pintype "passive"))
    )
    (net (code "216") (name "/J800_110") (class "Default")
      (node (ref "J800b") (pin "109") (pinfunction "IO_P_109") (pintype "passive"))
    )
    (net (code "217") (name "/J800_111") (class "Default")
      (node (ref "J800b") (pin "112") (pinfunction "IO_P_112") (pintype "passive"))
    )
    (net (code "218") (name "/J800_112") (class "Default")
      (node (ref "J800b") (pin "111") (pinfunction "IO_N_111") (pintype "passive"))
    )
    (net (code "219") (name "/J800_114") (class "Default")
      (node (ref "J800b") (pin "113") (pinfunction "GND_113") (pintype "passive"))
    )
    (net (code "220") (name "/J800_115") (class "Default")
      (node (ref "J800b") (pin "116") (pinfunction "VIN_IO_116") (pintype "passive"))
    )
    (net (code "221") (name "/J800_116") (class "Default")
      (node (ref "J800b") (pin "115") (pinfunction "SCLK_P_115") (pintype "passive"))
    )
    (net (code "222") (name "/J800_117") (class "Default")
      (node (ref "J800b") (pin "118") (pinfunction "IO_P_118") (pintype "passive"))
    )
    (net (code "223") (name "/J800_118") (class "Default")
      (node (ref "J800b") (pin "117") (pinfunction "SCLK_N_117") (pintype "passive"))
    )
    (net (code "224") (name "/J800_119") (class "Default")
      (node (ref "J800b") (pin "120") (pinfunction "IO_N_120") (pintype "passive"))
    )
    (net (code "225") (name "/J800_120") (class "Default")
      (node (ref "J800b") (pin "119") (pinfunction "IO_P_119") (pintype "passive"))
    )
    (net (code "226") (name "/J800_121") (class "Default")
      (node (ref "J800b") (pin "122") (pinfunction "SCLK_P_122") (pintype "passive"))
    )
    (net (code "227") (name "/J800_122") (class "Default")
      (node (ref "J800b") (pin "121") (pinfunction "IO_N_121") (pintype "passive"))
    )
    (net (code "228") (name "/J800_123") (class "Default")
      (node (ref "J800b") (pin "124") (pinfunction "SCLK_N_124") (pintype "passive"))
    )
    (net (code "229") (name "/J800_124") (class "Default")
      (node (ref "J800b") (pin "123") (pinfunction "VOUT_123") (pintype "passive"))
    )
    (net (code "230") (name "/J800_125") (class "Default")
      (node (ref "J800b") (pin "126") (pinfunction "GND_126") (pintype "passive"))
    )
    (net (code "231") (name "/J800_127") (class "Default")
      (node (ref "J800b") (pin "128") (pinfunction "IO_P_128") (pintype "passive"))
    )
    (net (code "232") (name "/J800_128") (class "Default")
      (node (ref "J800b") (pin "127") (pinfunction "IO_N_127") (pintype "passive"))
    )
    (net (code "233") (name "/J800_129") (class "Default")
      (node (ref "J800b") (pin "130") (pinfunction "IO_N_130") (pintype "passive"))
    )
    (net (code "234") (name "/J800_130") (class "Default")
      (node (ref "J800b") (pin "129") (pinfunction "IO_P_129") (pintype "passive"))
    )
    (net (code "235") (name "/J800_131") (class "Default")
      (node (ref "J800b") (pin "132") (pinfunction "IO_P_132") (pintype "passive"))
    )
    (net (code "236") (name "/J800_132") (class "Default")
      (node (ref "J800b") (pin "131") (pinfunction "IO_N_131") (pintype "passive"))
    )
    (net (code "237") (name "/J800_134") (class "Default")
      (node (ref "J800b") (pin "133") (pinfunction "GND_133") (pintype "passive"))
    )
    (net (code "238") (name "/J800_135") (class "Default")
      (node (ref "J800b") (pin "136") (pinfunction "VOUT_3V3_136") (pintype "passive"))
    )
    (net (code "239") (name "/J800_136") (class "Default")
      (node (ref "J800b") (pin "135") (pinfunction "IO_P_135") (pintype "passive"))
    )
    (net (code "240") (name "/J800_137") (class "Default")
      (node (ref "J800b") (pin "138") (pinfunction "IO_P_138") (pintype "passive"))
    )
    (net (code "241") (name "/J800_138") (class "Default")
      (node (ref "J800b") (pin "137") (pinfunction "IO_N_137") (pintype "passive"))
    )
    (net (code "242") (name "/J800_139") (class "Default")
      (node (ref "J800b") (pin "140") (pinfunction "IO_N_140") (pintype "passive"))
    )
    (net (code "243") (name "/J800_140") (class "Default")
      (node (ref "J800b") (pin "139") (pinfunction "IO_P_139") (pintype "passive"))
    )
    (net (code "244") (name "/J800_141") (class "Default")
      (node (ref "J800b") (pin "142") (pinfunction "IO_P_142") (pintype "passive"))
    )
    (net (code "245") (name "/J800_142") (class "Default")
      (node (ref "J800b") (pin "141") (pinfunction "IO_N_141") (pintype "passive"))
    )
    (net (code "246") (name "/J800_143") (class "Default")
      (node (ref "J800b") (pin "144") (pinfunction "IO_N_144") (pintype "passive"))
    )
    (net (code "247") (name "/J800_144") (class "Default")
      (node (ref "J800b") (pin "143") (pinfunction "VOUT_3V3_143") (pintype "passive"))
    )
    (net (code "248") (name "/J800_145") (class "Default")
      (node (ref "J800b") (pin "146") (pinfunction "GND_146") (pintype "passive"))
    )
    (net (code "249") (name "/J800_147") (class "Default")
      (node (ref "J800b") (pin "148") (pinfunction "PCLK_P_148") (pintype "passive"))
    )
    (net (code "250") (name "/J800_148") (class "Default")
      (node (ref "J800b") (pin "147") (pinfunction "IO_N_147") (pintype "passive"))
    )
    (net (code "251") (name "/J800_150") (class "Default")
      (node (ref "J800b") (pin "149") (pinfunction "GND_149") (pintype "passive"))
    )
    (net (code "252") (name "/J800_151") (class "Default")
      (node (ref "J800b") (pin "152") (pinfunction "GND_152") (pintype "passive"))
    )
    (net (code "253") (name "/J800_153") (class "Default")
      (node (ref "J800b") (pin "154") (pinfunction "IO_P_154") (pintype "passive"))
    )
    (net (code "254") (name "/J800_154") (class "Default")
      (node (ref "J800b") (pin "153") (pinfunction "SCLK_N_153") (pintype "passive"))
    )
    (net (code "255") (name "/J800_156") (class "Default")
      (node (ref "J800b") (pin "155") (pinfunction "GND_155") (pintype "passive"))
    )
    (net (code "256") (name "/J800_157") (class "Default")
      (node (ref "J800b") (pin "158") (pinfunction "VIN_IO_158") (pintype "passive"))
    )
    (net (code "257") (name "/J800_158") (class "Default")
      (node (ref "J800b") (pin "157") (pinfunction "IO_P_157") (pintype "passive"))
    )
    (net (code "258") (name "/J800_159") (class "Default")
      (node (ref "J800b") (pin "160") (pinfunction "IO_P_160") (pintype "passive"))
    )
    (net (code "259") (name "/J800_160") (class "Default")
      (node (ref "J800b") (pin "159") (pinfunction "IO_N_159") (pintype "passive"))
    )
    (net (code "260") (name "/J800_161") (class "Default")
      (node (ref "J800b") (pin "162") (pinfunction "IO_N_162") (pintype "passive"))
    )
    (net (code "261") (name "/J800_162") (class "Default")
      (node (ref "J800b") (pin "161") (pinfunction "IO_P_161") (pintype "passive"))
    )
    (net (code "262") (name "/J800_163") (class "Default")
      (node (ref "J800b") (pin "164") (pinfunction "IO_P_164") (pintype "passive"))
    )
    (net (code "263") (name "/J800_164") (class "Default")
      (node (ref "J800b") (pin "163") (pinfunction "IO_N_163") (pintype "passive"))
    )
    (net (code "264") (name "/J800_165") (class "Default")
      (node (ref "J800b") (pin "166") (pinfunction "IO_N_166") (pintype "passive"))
    )
    (net (code "265") (name "/J800_166") (class "Default")
      (node (ref "J800b") (pin "165") (pinfunction "VOUT_165") (pintype "passive"))
    )
    (net (code "266") (name "/J800_167") (class "Default")
      (node (ref "J800b") (pin "168") (pinfunction "GND_168") (pintype "passive"))
    )
    (net (code "267") (name "/JTAG_TCK") (class "Default")
      (node (ref "P0") (pin "13") (pinfunction "13_13") (pintype "passive"))
    )
    (net (code "268") (name "/JTAG_TDI") (class "Default")
      (node (ref "P0") (pin "7") (pinfunction "7_7") (pintype "passive"))
    )
    (net (code "269") (name "/JTAG_TDO") (class "Default")
      (node (ref "P0") (pin "11") (pinfunction "11_11") (pintype "passive"))
    )
    (net (code "270") (name "/JTAG_TMS") (class "Default")
      (node (ref "P0") (pin "9") (pinfunction "9_9") (pintype "passive"))
    )
    (net (code "271") (name "/MGT_CLK_1_N") (class "Default")
      (node (ref "J701b") (pin "5") (pinfunction "SCLK_N_5") (pintype "passive"))
    )
    (net (code "272") (name "/MGT_CLK_1_P") (class "Default")
      (node (ref "J701b") (pin "3") (pinfunction "SCLK_P_3") (pintype "passive"))
    )
    (net (code "273") (name "/MGT_CLK_2_N") (class "Default")
      (node (ref "J701b") (pin "11") (pinfunction "GND_11") (pintype "passive"))
    )
    (net (code "274") (name "/MGT_CLK_2_P") (class "Default")
      (node (ref "J701b") (pin "9") (pinfunction "IO_N_9") (pintype "passive"))
    )
    (net (code "275") (name "/MGT_RX0_N") (class "Default")
      (node (ref "J701b") (pin "19") (pinfunction "GND_19") (pintype "passive"))
    )
    (net (code "276") (name "/MGT_RX0_P") (class "Default")
      (node (ref "J701b") (pin "15") (pinfunction "GND_15") (pintype "passive"))
    )
    (net (code "277") (name "/MGT_RX1_N") (class "Default")
      (node (ref "J701b") (pin "27") (pinfunction "GND_27") (pintype "passive"))
    )
    (net (code "278") (name "/MGT_RX1_P") (class "Default")
      (node (ref "J701b") (pin "23") (pinfunction "GND_23") (pintype "passive"))
    )
    (net (code "279") (name "/MGT_RX2_N") (class "Default")
      (node (ref "J701b") (pin "35") (pinfunction "GND_35") (pintype "passive"))
    )
    (net (code "280") (name "/MGT_RX2_P") (class "Default")
      (node (ref "J701b") (pin "31") (pinfunction "GND_31") (pintype "passive"))
    )
    (net (code "281") (name "/MGT_RX3_N") (class "Default")
      (node (ref "J701b") (pin "43") (pinfunction "GND_43") (pintype "passive"))
    )
    (net (code "282") (name "/MGT_RX3_P") (class "Default")
      (node (ref "J701b") (pin "39") (pinfunction "GND_39") (pintype "passive"))
    )
    (net (code "283") (name "/MGT_TX0_N") (class "Default")
      (node (ref "J701b") (pin "18") (pinfunction "GND_18") (pintype "passive"))
    )
    (net (code "284") (name "/MGT_TX0_P") (class "Default")
      (node (ref "J701b") (pin "14") (pinfunction "GND_14") (pintype "passive"))
    )
    (net (code "285") (name "/MGT_TX1_N") (class "Default")
      (node (ref "J701b") (pin "26") (pinfunction "GND_26") (pintype "passive"))
    )
    (net (code "286") (name "/MGT_TX1_P") (class "Default")
      (node (ref "J701b") (pin "22") (pinfunction "GND_22") (pintype "passive"))
    )
    (net (code "287") (name "/MGT_TX2_N") (class "Default")
      (node (ref "J701b") (pin "34") (pinfunction "GND_34") (pintype "passive"))
    )
    (net (code "288") (name "/MGT_TX2_P") (class "Default")
      (node (ref "J701b") (pin "30") (pinfunction "GND_30") (pintype "passive"))
    )
    (net (code "289") (name "/MGT_TX3_N") (class "Default")
      (node (ref "J701b") (pin "42") (pinfunction "GND_42") (pintype "passive"))
    )
    (net (code "290") (name "/MGT_TX3_P") (class "Default")
      (node (ref "J701b") (pin "38") (pinfunction "GND_38") (pintype "passive"))
    )
    (net (code "291") (name "/SCLK{slash}MGT_RCLK_N") (class "Default")
      (node (ref "J701b") (pin "6") (pinfunction "MGT_CLK_N_6") (pintype "passive"))
    )
    (net (code "292") (name "/SCLK{slash}MGT_RCLK_P") (class "Default")
      (node (ref "J701b") (pin "4") (pinfunction "MGT_CLK_P_4") (pintype "passive"))
    )
    (net (code "293") (name "DGND") (class "Default")
      (node (ref "J701b") (pin "1") (pinfunction "GND_1") (pintype "passive"))
      (node (ref "J701b") (pin "106") (pinfunction "IO_N_106") (pintype "passive"))
      (node (ref "J701b") (pin "117") (pinfunction "IO_P_117") (pintype "passive"))
      (node (ref "J701b") (pin "12") (pinfunction "MGT_CLK_N_12") (pintype "passive"))
      (node (ref "J701b") (pin "122") (pinfunction "IO_N_122") (pintype "passive"))
      (node (ref "J701b") (pin "13") (pinfunction "MGT_TX_P_13") (pintype "passive"))
      (node (ref "J701b") (pin "133") (pinfunction "IO_P_133") (pintype "passive"))
      (node (ref "J701b") (pin "138") (pinfunction "IO_N_138") (pintype "passive"))
      (node (ref "J701b") (pin "145") (pinfunction "IO_P_145") (pintype "passive"))
      (node (ref "J701b") (pin "150") (pinfunction "IO_N_150") (pintype "passive"))
      (node (ref "J701b") (pin "16") (pinfunction "MGT_RX_P_16") (pintype "passive"))
      (node (ref "J701b") (pin "162") (pinfunction "IO_N_162") (pintype "passive"))
      (node (ref "J701b") (pin "17") (pinfunction "MGT_TX_N_17") (pintype "passive"))
      (node (ref "J701b") (pin "2") (pinfunction "GND_2") (pintype "passive"))
      (node (ref "J701b") (pin "20") (pinfunction "MGT_RX_N_20") (pintype "passive"))
      (node (ref "J701b") (pin "21") (pinfunction "MGT_TX_P_21") (pintype "passive"))
      (node (ref "J701b") (pin "24") (pinfunction "MGT_RX_P_24") (pintype "passive"))
      (node (ref "J701b") (pin "25") (pinfunction "MGT_TX_N_25") (pintype "passive"))
      (node (ref "J701b") (pin "28") (pinfunction "MGT_RX_N_28") (pintype "passive"))
      (node (ref "J701b") (pin "29") (pinfunction "MGT_TX_P_29") (pintype "passive"))
      (node (ref "J701b") (pin "32") (pinfunction "MGT_RX_P_32") (pintype "passive"))
      (node (ref "J701b") (pin "33") (pinfunction "MGT_TX_N_33") (pintype "passive"))
      (node (ref "J701b") (pin "36") (pinfunction "MGT_RX_N_36") (pintype "passive"))
      (node (ref "J701b") (pin "37") (pinfunction "MGT_TX_P_37") (pintype "passive"))
      (node (ref "J701b") (pin "40") (pinfunction "MGT_RX_P_40") (pintype "passive"))
      (node (ref "J701b") (pin "41") (pinfunction "MGT_TX_N_41") (pintype "passive"))
      (node (ref "J701b") (pin "44") (pinfunction "MGT_RX_N_44") (pintype "passive"))
      (node (ref "J701b") (pin "45") (pinfunction "IO_P_45") (pintype "passive"))
      (node (ref "J701b") (pin "50") (pinfunction "IO_N_50") (pintype "passive"))
      (node (ref "J701b") (pin "57") (pinfunction "PCLK_P_57") (pintype "passive"))
      (node (ref "J701b") (pin "62") (pinfunction "IO_N_62") (pintype "passive"))
      (node (ref "J701b") (pin "69") (pinfunction "IO_P_69") (pintype "passive"))
      (node (ref "J701b") (pin "74") (pinfunction "IO_N_74") (pintype "passive"))
      (node (ref "J701b") (pin "81") (pinfunction "SCLK_P_81") (pintype "passive"))
      (node (ref "J701b") (pin "86") (pinfunction "IO_N_86") (pintype "passive"))
      (node (ref "J701b") (pin "97") (pinfunction "IO_P_97") (pintype "passive"))
      (node (ref "J800b") (pin "1") (pinfunction "GND_1") (pintype "passive"))
      (node (ref "J800b") (pin "105") (pinfunction "IO_P_105") (pintype "passive"))
      (node (ref "J800b") (pin "114") (pinfunction "IO_N_114") (pintype "passive"))
      (node (ref "J800b") (pin "12") (pinfunction "REFCLK_N_12") (pintype "passive"))
      (node (ref "J800b") (pin "125") (pinfunction "IO_P_125") (pintype "passive"))
      (node (ref "J800b") (pin "13") (pinfunction "MGT_TX_P_13") (pintype "passive"))
      (node (ref "J800b") (pin "134") (pinfunction "IO_N_134") (pintype "passive"))
      (node (ref "J800b") (pin "145") (pinfunction "IO_P_145") (pintype "passive"))
      (node (ref "J800b") (pin "150") (pinfunction "PCLK_N_150") (pintype "passive"))
      (node (ref "J800b") (pin "151") (pinfunction "SCLK_P_151") (pintype "passive"))
      (node (ref "J800b") (pin "156") (pinfunction "IO_N_156") (pintype "passive"))
      (node (ref "J800b") (pin "16") (pinfunction "MGT_RX_P_16") (pintype "passive"))
      (node (ref "J800b") (pin "167") (pinfunction "RSVD_167") (pintype "passive"))
      (node (ref "J800b") (pin "17") (pinfunction "MGT_TX_N_17") (pintype "passive"))
      (node (ref "J800b") (pin "2") (pinfunction "GND_2") (pintype "passive"))
      (node (ref "J800b") (pin "20") (pinfunction "MGT_RX_N_20") (pintype "passive"))
      (node (ref "J800b") (pin "21") (pinfunction "MGT_TX_P_21") (pintype "passive"))
      (node (ref "J800b") (pin "24") (pinfunction "MGT_RX_P_24") (pintype "passive"))
      (node (ref "J800b") (pin "25") (pinfunction "MGT_TX_N_25") (pintype "passive"))
      (node (ref "J800b") (pin "28") (pinfunction "MGT_RX_N_28") (pintype "passive"))
      (node (ref "J800b") (pin "29") (pinfunction "MGT_TX_P_29") (pintype "passive"))
      (node (ref "J800b") (pin "32") (pinfunction "MGT_RX_P_32") (pintype "passive"))
      (node (ref "J800b") (pin "33") (pinfunction "MGT_TX_N_33") (pintype "passive"))
      (node (ref "J800b") (pin "36") (pinfunction "MGT_RX_N_36") (pintype "passive"))
      (node (ref "J800b") (pin "37") (pinfunction "MGT_TX_P_37") (pintype "passive"))
      (node (ref "J800b") (pin "40") (pinfunction "MGT_RX_P_40") (pintype "passive"))
      (node (ref "J800b") (pin "41") (pinfunction "MGT_TX_N_41") (pintype "passive"))
      (node (ref "J800b") (pin "44") (pinfunction "MGT_RX_N_44") (pintype "passive"))
      (node (ref "J800b") (pin "45") (pinfunction "IO_P_45") (pintype "passive"))
      (node (ref "J800b") (pin "50") (pinfunction "IO_N_50") (pintype "passive"))
      (node (ref "J800b") (pin "51") (pinfunction "IO_P_51") (pintype "passive"))
      (node (ref "J800b") (pin "56") (pinfunction "IO_N_56") (pintype "passive"))
      (node (ref "J800b") (pin "57") (pinfunction "IO_P_57") (pintype "passive"))
      (node (ref "J800b") (pin "62") (pinfunction "IO_N_62") (pintype "passive"))
      (node (ref "J800b") (pin "63") (pinfunction "IO_P_63") (pintype "passive"))
      (node (ref "J800b") (pin "68") (pinfunction "IO_N_68") (pintype "passive"))
      (node (ref "J800b") (pin "69") (pinfunction "SCLK_P_69") (pintype "passive"))
      (node (ref "J800b") (pin "74") (pinfunction "SCLK_N_74") (pintype "passive"))
      (node (ref "J800b") (pin "85") (pinfunction "IO_P_85") (pintype "passive"))
      (node (ref "J800b") (pin "94") (pinfunction "IO_N_94") (pintype "passive"))
      (node (ref "P0") (pin "10") (pinfunction "10_10") (pintype "passive"))
      (node (ref "P0") (pin "12") (pinfunction "12_12") (pintype "passive"))
      (node (ref "P0") (pin "14") (pinfunction "14_14") (pintype "passive"))
      (node (ref "P0") (pin "2") (pinfunction "2_2") (pintype "passive"))
      (node (ref "P0") (pin "4") (pinfunction "4_4") (pintype "passive"))
      (node (ref "P0") (pin "6") (pinfunction "6_6") (pintype "passive"))
      (node (ref "P0") (pin "8") (pinfunction "8_8") (pintype "passive"))
      (node (ref "R21") (pin "1") (pintype "passive"))
      (node (ref "R23") (pin "1") (pintype "passive"))
      (node (ref "R50") (pin "1") (pintype "passive"))
      (node (ref "R51") (pin "1") (pintype "passive"))
      (node (ref "R52") (pin "1") (pintype "passive"))
      (node (ref "R53") (pin "1") (pintype "passive"))
      (node (ref "R58") (pin "1") (pintype "passive"))
      (node (ref "R59") (pin "1") (pintype "passive"))
      (node (ref "R60") (pin "1") (pintype "passive"))
      (node (ref "R61") (pin "1") (pintype "passive"))
      (node (ref "R62") (pin "1") (pintype "passive"))
      (node (ref "R63") (pin "1") (pintype "passive"))
      (node (ref "R64") (pin "1") (pintype "passive"))
      (node (ref "R65") (pin "1") (pintype "passive"))
      (node (ref "R66") (pin "1") (pintype "passive"))
      (node (ref "R67") (pin "1") (pintype "passive"))
    )
    (net (code "294") (name "DVDD25") (class "Default")
      (node (ref "J701b") (pin "139") (pinfunction "IO_P_139") (pintype "passive"))
      (node (ref "J701b") (pin "144") (pinfunction "IO_N_144") (pintype "passive"))
      (node (ref "J701b") (pin "63") (pinfunction "IO_P_63") (pintype "passive"))
      (node (ref "J701b") (pin "68") (pinfunction "IO_N_68") (pintype "passive"))
      (node (ref "J701b") (pin "87") (pinfunction "IO_P_87") (pintype "passive"))
      (node (ref "J701b") (pin "96") (pinfunction "IO_N_96") (pintype "passive"))
    )
    (net (code "295") (name "unconnected-(J701b-IO_N-Pad56)") (class "Default")
      (node (ref "J701b") (pin "56") (pinfunction "IO_N_56") (pintype "passive"))
    )
    (net (code "296") (name "unconnected-(J701b-IO_N-Pad116)") (class "Default")
      (node (ref "J701b") (pin "116") (pinfunction "IO_N_116") (pintype "passive"))
    )
    (net (code "297") (name "unconnected-(J701b-IO_P-Pad7)") (class "Default")
      (node (ref "J701b") (pin "7") (pinfunction "IO_P_7") (pintype "passive"))
    )
    (net (code "298") (name "unconnected-(J701b-IO_P-Pad51)") (class "Default")
      (node (ref "J701b") (pin "51") (pinfunction "IO_P_51") (pintype "passive"))
    )
    (net (code "299") (name "unconnected-(J701b-IO_P-Pad75)") (class "Default")
      (node (ref "J701b") (pin "75") (pinfunction "IO_P_75") (pintype "passive"))
    )
    (net (code "300") (name "unconnected-(J701b-IO_P-Pad107)") (class "Default")
      (node (ref "J701b") (pin "107") (pinfunction "IO_P_107") (pintype "passive"))
    )
    (net (code "301") (name "unconnected-(J701b-IO_P-Pad157)") (class "Default")
      (node (ref "J701b") (pin "157") (pinfunction "IO_P_157") (pintype "passive"))
    )
    (net (code "302") (name "unconnected-(J701b-PCLK_N-Pad80)") (class "Default")
      (node (ref "J701b") (pin "80") (pinfunction "PCLK_N_80") (pintype "passive"))
    )
    (net (code "303") (name "unconnected-(J701b-PCLK_P-Pad151)") (class "Default")
      (node (ref "J701b") (pin "151") (pinfunction "PCLK_P_151") (pintype "passive"))
    )
    (net (code "304") (name "unconnected-(J701b-SCLK_N-Pad156)") (class "Default")
      (node (ref "J701b") (pin "156") (pinfunction "SCLK_N_156") (pintype "passive"))
    )
    (net (code "305") (name "unconnected-(J701b-VMON-Pad167)") (class "Default")
      (node (ref "J701b") (pin "167") (pinfunction "VMON_167") (pintype "passive"))
    )
    (net (code "306") (name "unconnected-(J701b-VMON-Pad168)") (class "Default")
      (node (ref "J701b") (pin "168") (pinfunction "VMON_168") (pintype "passive"))
    )
    (net (code "307") (name "unconnected-(J701b-VOUT-Pad128)") (class "Default")
      (node (ref "J701b") (pin "128") (pinfunction "VOUT_128") (pintype "passive"))
    )
    (net (code "308") (name "unconnected-(J701b-VOUT_3V3-Pad127)") (class "Default")
      (node (ref "J701b") (pin "127") (pinfunction "VOUT_3V3_127") (pintype "passive"))
    )
  )
)
